# 8_GPS.net
KiCad netlist of a schematic drawn in Altium Designer
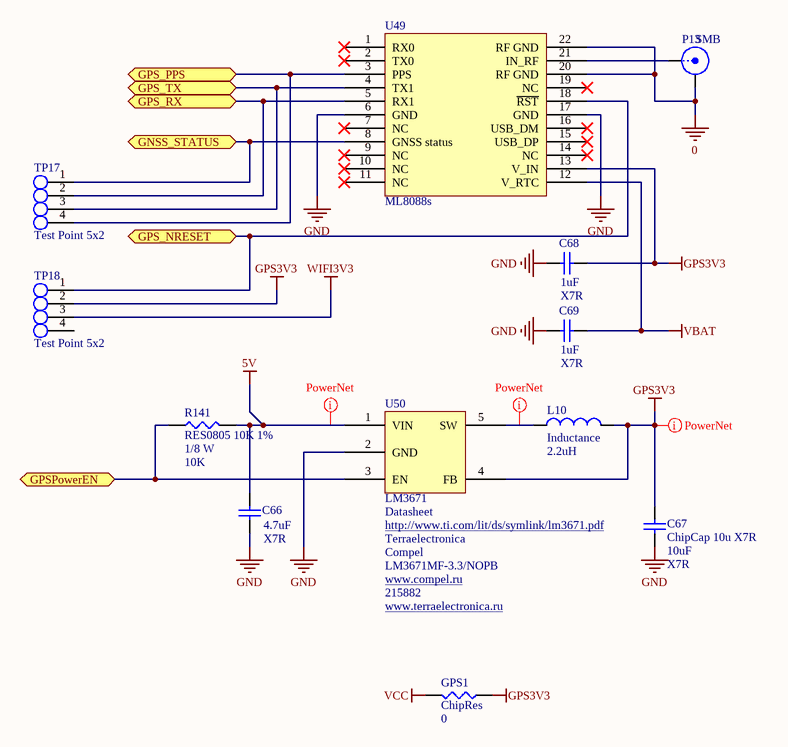
[diagram p0: [8] GPS.SchDoc]

(export (version "E")
  (design (tool "Eeschema 10.0.6"))
  (components
    (comp (ref "C66")
      (value "4.7uF")
      (footprint "CAP1210")
      (description "Surface-mount ceramic multilayer capacitor")
      (fields (field (name "VOLTAGE") "25V") (field (name "TOLERANCE") "10%") (field (name "TYPE") "X7R"))
      (libsource (lib "Capacitors") (part "ChipCap 4.7uF X7R"))
    )
    (comp (ref "C67")
      (value "ChipCap 10u X7R")
      (footprint "CAP1210")
      (description "Surface-mount ceramic multilayer capacitor")
      (fields
        (field (name "VOLTAGE") "25V")
        (field (name "TOLERANCE") "10%")
        (field (name "ALTIUM_VALUE") "10uF")
        (field (name "TYPE") "X7R")
      )
      (libsource (lib "Capacitors") (part "ChipCap 10uF X7R"))
    )
    (comp (ref "C68")
      (value "1uF")
      (footprint "CAP0805")
      (description "Surface-mount ceramic multilayer capacitor")
      (fields (field (name "VOLTAGE") "16V") (field (name "TOLERANCE") "5%") (field (name "TYPE") "X7R"))
      (libsource (lib "Capacitors") (part "CAP0805 1uF X7R"))
    )
    (comp (ref "C69")
      (value "1uF")
      (footprint "CAP0805")
      (description "Surface-mount ceramic multilayer capacitor")
      (fields (field (name "VOLTAGE") "16V") (field (name "TOLERANCE") "5%") (field (name "TYPE") "X7R"))
      (libsource (lib "Capacitors") (part "CAP0805 1uF X7R"))
    )
    (comp (ref "GPS1")
      (value "ChipRes")
      (footprint "RES0805")
      (description "Chip resistor")
      (fields (field (name "ALTIUM_VALUE") "0"))
      (libsource (lib "Common Devices") (part "ChipRes"))
    )
    (comp (ref "L10")
      (value "Inductance")
      (footprint "CDRH2D14")
      (fields (field (name "ALTIUM_VALUE") "2.2uH"))
      (libsource (lib "Common Devices") (part "ChipInductance"))
    )
    (comp (ref "P13")
      (value "SMB")
      (footprint "SMB_V-RJ45")
      (description "SMB Straight Connector")
      (fields (field (name "PUBLISHER") "Altium Limited"))
      (libsource (lib "Miscellaneous Connectors") (part "SMB"))
    )
    (comp (ref "R141")
      (value "RES0805 10K 1%")
      (footprint "RES0805")
      (description "Think Film Chip resistor")
      (fields
        (field (name "TOLERANCE") "1%")
        (field (name "MANUFACTURER PART NUMBER") "RC0805FR-0710KL")
        (field (name "RATING") "1/8 W")
        (field (name "ALTIUM_VALUE") "10K")
      )
      (libsource (lib "Resistors") (part "RES0805 10K 1%"))
    )
    (comp (ref "TP17")
      (value "Test Point 5x2")
      (footprint "PG-1.5-13.5-4P-2.54PH")
      (libsource (lib "Connectors") (part "PG-1.5-13.5-4P-2.54PH"))
    )
    (comp (ref "TP18")
      (value "Test Point 5x2")
      (footprint "PG-1.5-13.5-4P-2.54PH")
      (libsource (lib "Connectors") (part "PG-1.5-13.5-4P-2.54PH"))
    )
    (comp (ref "U49")
      (value "ML8088s")
      (footprint "ML8088s")
      (description "GPS Receiver")
      (libsource (lib "GPS") (part "ML8088"))
    )
    (comp (ref "U50")
      (value "LM3671")
      (footprint "SOT23-5")
      (description "600-mA Step-Down DC-DC Converter")
      (fields
        (field (name "COMPONENTLINK1DESCRIPTION") "Datasheet")
        (field (name "COMPONENTLINK1URL") "http://www.ti.com/lit/ds/symlink/lm3671.pdf")
        (field (name "SUPPLIER 1") "Terraelectronica")
        (field (name "SUPPLIER 2") "Compel")
        (field (name "SUPPLIER PART NUMBER 2") "LM3671MF-3.3/NOPB")
        (field (name "SUPPLIER URL 2") "www.compel.ru")
        (field (name "SUPPLIER PART NUMBER 1") "215882")
        (field (name "SUPPLIER URL 1") "www.terraelectronica.ru")
      )
      (libsource (lib "TI DC-DC Convertors") (part "LM3671MF"))
    )
  )
  (nets
    (net (code "1") (name "/GNSS_STATUS") (class "Default")
      (node (ref "TP17") (pin "1") (pinfunction "1_1") (pintype "passive"))
      (node (ref "U49") (pin "8") (pinfunction "GNSS_status_8") (pintype "passive"))
    )
    (net (code "2") (name "/GPSPowerEN") (class "Default")
      (node (ref "R141") (pin "1") (pintype "passive"))
      (node (ref "U50") (pin "3") (pinfunction "EN_3") (pintype "passive"))
    )
    (net (code "3") (name "/GPS_NRESET") (class "Default")
      (node (ref "TP18") (pin "1") (pinfunction "1_1") (pintype "passive"))
      (node (ref "U49") (pin "18") (pinfunction "~{RST}_18") (pintype "passive"))
    )
    (net (code "4") (name "/GPS_PPS") (class "Default")
      (node (ref "TP17") (pin "4") (pinfunction "4_4") (pintype "passive"))
      (node (ref "U49") (pin "3") (pinfunction "PPS_3") (pintype "passive"))
    )
    (net (code "5") (name "/GPS_RX") (class "Default")
      (node (ref "TP17") (pin "2") (pinfunction "2_2") (pintype "passive"))
      (node (ref "U49") (pin "5") (pinfunction "RX1_5") (pintype "passive"))
    )
    (net (code "6") (name "/GPS_TX") (class "Default")
      (node (ref "TP17") (pin "3") (pinfunction "3_3") (pintype "passive"))
      (node (ref "U49") (pin "4") (pinfunction "TX1_4") (pintype "passive"))
    )
    (net (code "7") (name "0") (class "Default")
      (node (ref "P13") (pin "2") (pinfunction "Y_2") (pintype "passive"))
      (node (ref "U49") (pin "20") (pinfunction "RF_GND_20") (pintype "passive"))
      (node (ref "U49") (pin "22") (pinfunction "RF_GND_22") (pintype "passive"))
    )
    (net (code "8") (name "5V") (class "Default")
      (node (ref "C66") (pin "2") (pinfunction "2_2") (pintype "passive"))
      (node (ref "R141") (pin "2") (pintype "passive"))
      (node (ref "U50") (pin "1") (pinfunction "VIN_1") (pintype "passive"))
    )
    (net (code "9") (name "GND") (class "Default")
      (node (ref "C66") (pin "1") (pinfunction "1_1") (pintype "passive"))
      (node (ref "C67") (pin "1") (pinfunction "1_1") (pintype "passive"))
      (node (ref "C68") (pin "1") (pinfunction "1_1") (pintype "passive"))
      (node (ref "C69") (pin "1") (pinfunction "1_1") (pintype "passive"))
      (node (ref "U49") (pin "17") (pinfunction "GND_17") (pintype "passive"))
      (node (ref "U49") (pin "6") (pinfunction "GND_6") (pintype "passive"))
      (node (ref "U50") (pin "2") (pinfunction "GND_2") (pintype "passive"))
    )
    (net (code "10") (name "GPS3V3") (class "Default")
      (node (ref "C67") (pin "2") (pinfunction "2_2") (pintype "passive"))
      (node (ref "C68") (pin "2") (pinfunction "2_2") (pintype "passive"))
      (node (ref "GPS1") (pin "1") (pintype "passive"))
      (node (ref "L10") (pin "1") (pintype "passive"))
      (node (ref "TP18") (pin "2") (pinfunction "2_2") (pintype "passive"))
      (node (ref "U49") (pin "13") (pinfunction "V_IN_13") (pintype "passive"))
      (node (ref "U50") (pin "4") (pinfunction "FB_4") (pintype "passive"))
    )
    (net (code "11") (name "Net-(P13-X)") (class "Default")
      (node (ref "P13") (pin "1") (pinfunction "X_1") (pintype "passive"))
      (node (ref "U49") (pin "21") (pinfunction "IN_RF_21") (pintype "passive"))
    )
    (net (code "12") (name "Net-(U50-SW)") (class "Default")
      (node (ref "L10") (pin "2") (pintype "passive"))
      (node (ref "U50") (pin "5") (pinfunction "SW_5") (pintype "passive"))
    )
    (net (code "13") (name "VBAT") (class "Default")
      (node (ref "C69") (pin "2") (pinfunction "2_2") (pintype "passive"))
      (node (ref "U49") (pin "12") (pinfunction "V_RTC_12") (pintype "passive"))
    )
    (net (code "14") (name "VCC") (class "Default") (node (ref "GPS1") (pin "2") (pintype "passive")))
    (net (code "15") (name "WIFI3V3") (class "Default")
      (node (ref "TP18") (pin "3") (pinfunction "3_3") (pintype "passive"))
    )
    (net (code "16") (name "unconnected-(TP18-Pad4)") (class "Default")
      (node (ref "TP18") (pin "4") (pinfunction "4_4") (pintype "passive"))
    )
    (net (code "17") (name "unconnected-(U49-NC-Pad7)") (class "Default")
      (node (ref "U49") (pin "7") (pinfunction "NC_7") (pintype "passive+no_connect"))
    )
    (net (code "18") (name "unconnected-(U49-NC-Pad9)") (class "Default")
      (node (ref "U49") (pin "9") (pinfunction "NC_9") (pintype "passive+no_connect"))
    )
    (net (code "19") (name "unconnected-(U49-NC-Pad10)") (class "Default")
      (node (ref "U49") (pin "10") (pinfunction "NC_10") (pintype "passive+no_connect"))
    )
    (net (code "20") (name "unconnected-(U49-NC-Pad11)") (class "Default")
      (node (ref "U49") (pin "11") (pinfunction "NC_11") (pintype "passive+no_connect"))
    )
    (net (code "21") (name "unconnected-(U49-NC-Pad14)") (class "Default")
      (node (ref "U49") (pin "14") (pinfunction "NC_14") (pintype "passive+no_connect"))
    )
    (net (code "22") (name "unconnected-(U49-NC-Pad19)") (class "Default")
      (node (ref "U49") (pin "19") (pinfunction "NC_19") (pintype "passive+no_connect"))
    )
    (net (code "23") (name "unconnected-(U49-RX0-Pad1)") (class "Default")
      (node (ref "U49") (pin "1") (pinfunction "RX0_1") (pintype "passive+no_connect"))
    )
    (net (code "24") (name "unconnected-(U49-TX0-Pad2)") (class "Default")
      (node (ref "U49") (pin "2") (pinfunction "TX0_2") (pintype "passive+no_connect"))
    )
    (net (code "25") (name "unconnected-(U49-USB_DM-Pad16)") (class "Default")
      (node (ref "U49") (pin "16") (pinfunction "USB_DM_16") (pintype "passive+no_connect"))
    )
    (net (code "26") (name "unconnected-(U49-USB_DP-Pad15)") (class "Default")
      (node (ref "U49") (pin "15") (pinfunction "USB_DP_15") (pintype "passive+no_connect"))
    )
  )
)
